# IR.net
KiCad netlist of a schematic drawn in EAGLE
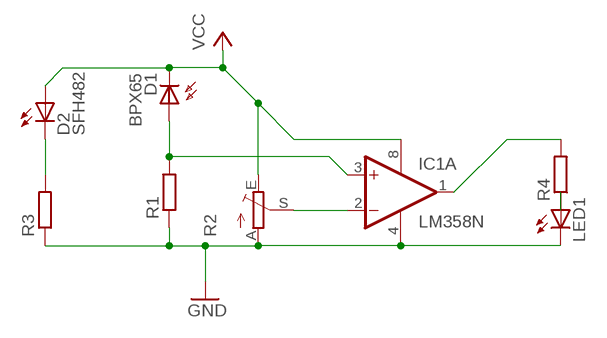
[diagram p0: schematic, sheet 1]

(export (version "E")
  (design (tool "Eeschema 10.0.6"))
  (components
    (comp (ref "D1")
      (value "BPX65")
      (footprint "eagle-import:BPX65")
      (fields (field (name "MPN") "BPX65."))
      (libsource (lib "eagle-import") (part "BPX65"))
    )
    (comp (ref "D2")
      (value "SFH482")
      (footprint "eagle-import:SFH482")
      (libsource (lib "eagle-import") (part "SFH482"))
    )
    (comp (ref "IC1")
      (value "LM358N")
      (footprint "eagle-import:DIL08")
      (libsource (lib "eagle-import") (part "LM358N"))
    )
    (comp (ref "LED1")
      (value "LED3MM")
      (footprint "eagle-import:LED3MM")
      (libsource (lib "eagle-import") (part "LED3MM"))
    )
    (comp (ref "R1")
      (value "R-EU_0204/7")
      (footprint "eagle-import:0204_7")
      (libsource (lib "eagle-import") (part "R-EU_0204/7"))
    )
    (comp (ref "R2")
      (value "TRIM_EU-B25P")
      (footprint "eagle-import:B25P")
      (libsource (lib "eagle-import") (part "TRIM_EU-B25P"))
    )
    (comp (ref "R3")
      (value "R-EU_0204/7")
      (footprint "eagle-import:0204_7")
      (libsource (lib "eagle-import") (part "R-EU_0204/7"))
    )
    (comp (ref "R4")
      (value "R-EU_0204/7")
      (footprint "eagle-import:0204_7")
      (libsource (lib "eagle-import") (part "R-EU_0204/7"))
    )
  )
  (nets
    (net (code "1") (name "GND") (class "Default")
      (node (ref "IC1") (pin "4") (pinfunction "V-_4") (pintype "power_in"))
      (node (ref "LED1") (pin "K") (pinfunction "C_K") (pintype "passive"))
      (node (ref "R1") (pin "1") (pinfunction "1_1") (pintype "passive"))
      (node (ref "R2") (pin "A") (pinfunction "A_A") (pintype "passive"))
      (node (ref "R3") (pin "1") (pinfunction "1_1") (pintype "passive"))
    )
    (net (code "2") (name "Net-(D2-C)") (class "Default")
      (node (ref "D2") (pin "K") (pinfunction "C_K") (pintype "passive"))
      (node (ref "R3") (pin "2") (pinfunction "2_2") (pintype "passive"))
    )
    (net (code "3") (name "Net-(IC1A-+IN)") (class "Default")
      (node (ref "D1") (pin "A") (pinfunction "A_A") (pintype "passive"))
      (node (ref "IC1") (pin "3") (pinfunction "+IN_3") (pintype "input"))
      (node (ref "R1") (pin "2") (pinfunction "2_2") (pintype "passive"))
    )
    (net (code "4") (name "Net-(IC1A--IN)") (class "Default")
      (node (ref "IC1") (pin "2") (pinfunction "-IN_2") (pintype "input"))
      (node (ref "R2") (pin "S") (pinfunction "S_S") (pintype "passive"))
    )
    (net (code "5") (name "Net-(IC1A-OUT)") (class "Default")
      (node (ref "IC1") (pin "1") (pinfunction "OUT_1") (pintype "output"))
      (node (ref "R4") (pin "2") (pinfunction "2_2") (pintype "passive"))
    )
    (net (code "6") (name "Net-(LED1-PadA)") (class "Default")
      (node (ref "LED1") (pin "A") (pinfunction "A_A") (pintype "passive"))
      (node (ref "R4") (pin "1") (pinfunction "1_1") (pintype "passive"))
    )
    (net (code "7") (name "VCC") (class "Default")
      (node (ref "D1") (pin "K") (pinfunction "C_K") (pintype "passive"))
      (node (ref "D2") (pin "A") (pinfunction "A_A") (pintype "passive"))
      (node (ref "IC1") (pin "8") (pinfunction "V+_8") (pintype "power_in"))
      (node (ref "R2") (pin "E") (pinfunction "E_E") (pintype "passive"))
    )
  )
)
